# esp-wifisensor.net
KiCad netlist of a schematic drawn in EAGLE
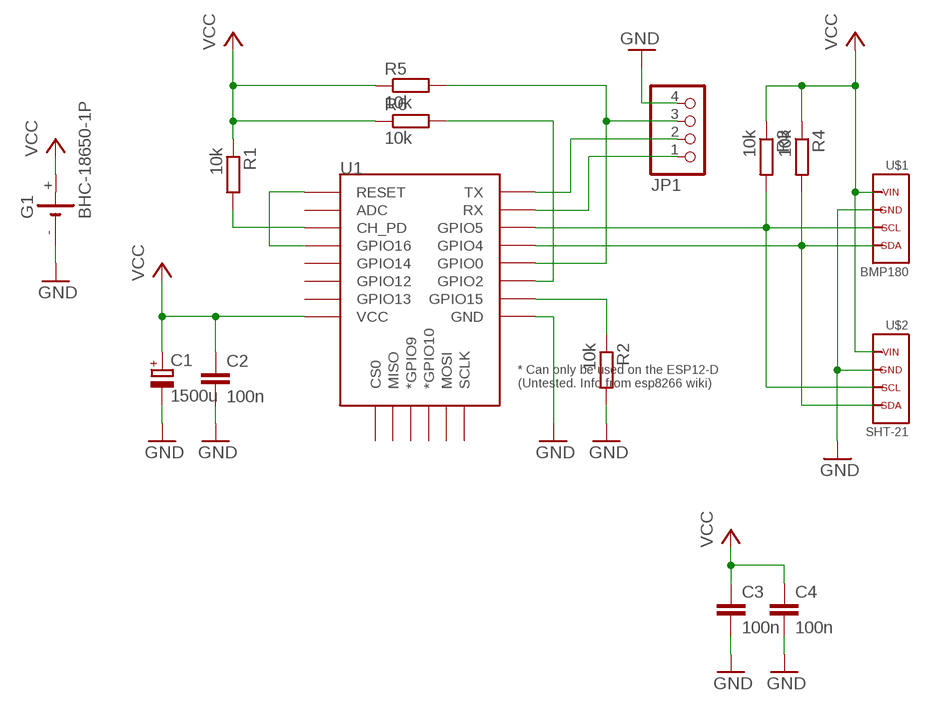
[diagram p0: schematic, sheet 1]

(export (version "E")
  (design (tool "Eeschema 10.0.6"))
  (components
    (comp (ref "C1")
      (value "1500u")
      (footprint "eagle-import:E5-13")
      (libsource (lib "eagle-import") (part "CPOL-EUE5-13"))
    )
    (comp (ref "C2")
      (value "100n")
      (footprint "eagle-import:C1206K")
      (libsource (lib "eagle-import") (part "C-EUC1206K"))
    )
    (comp (ref "C3")
      (value "100n")
      (footprint "eagle-import:C1206K")
      (libsource (lib "eagle-import") (part "C-EUC1206K"))
    )
    (comp (ref "C4")
      (value "100n")
      (footprint "eagle-import:C1206K")
      (libsource (lib "eagle-import") (part "C-EUC1206K"))
    )
    (comp (ref "G1")
      (value "BHC-18650-1P")
      (footprint "eagle-import:BHC-18650-1P")
      (libsource (lib "eagle-import") (part "BHC-18650-1P"))
    )
    (comp (ref "JP1")
      (value "PINHD-1X4")
      (footprint "eagle-import:1X04")
      (libsource (lib "eagle-import") (part "PINHD-1X4"))
    )
    (comp (ref "R1")
      (value "10k")
      (footprint "eagle-import:M1206")
      (libsource (lib "eagle-import") (part "R-EU_M1206"))
    )
    (comp (ref "R2")
      (value "10k")
      (footprint "eagle-import:M1206")
      (libsource (lib "eagle-import") (part "R-EU_M1206"))
    )
    (comp (ref "R3")
      (value "10k")
      (footprint "eagle-import:M1206")
      (libsource (lib "eagle-import") (part "R-EU_M1206"))
    )
    (comp (ref "R4")
      (value "10k")
      (footprint "eagle-import:M1206")
      (libsource (lib "eagle-import") (part "R-EU_M1206"))
    )
    (comp (ref "R5")
      (value "10k")
      (footprint "eagle-import:M1206")
      (libsource (lib "eagle-import") (part "R-EU_M1206"))
    )
    (comp (ref "R6")
      (value "10k")
      (footprint "eagle-import:M1206")
      (libsource (lib "eagle-import") (part "R-EU_M1206"))
    )
    (comp (ref "U$1")
      (value "BMP180")
      (footprint "eagle-import:BMP180")
      (libsource (lib "eagle-import") (part "BMP180"))
    )
    (comp (ref "U$2")
      (value "SHT-21")
      (footprint "eagle-import:SHT-21")
      (libsource (lib "eagle-import") (part "SHT-21"))
    )
    (comp (ref "U1")
      (value "ESP12ESMD")
      (footprint "eagle-import:ESP12E-SMD")
      (libsource (lib "eagle-import") (part "ESP12ESMD"))
    )
  )
  (nets
    (net (code "1") (name "GND") (class "Default")
      (node (ref "C1") (pin "-") (pinfunction "-_-") (pintype "passive"))
      (node (ref "C2") (pin "2") (pinfunction "2_2") (pintype "passive"))
      (node (ref "C3") (pin "2") (pinfunction "2_2") (pintype "passive"))
      (node (ref "C4") (pin "2") (pinfunction "2_2") (pintype "passive"))
      (node (ref "G1") (pin "-") (pinfunction "-_-") (pintype "passive"))
      (node (ref "JP1") (pin "4") (pinfunction "4_4") (pintype "passive"))
      (node (ref "R2") (pin "2") (pinfunction "2_2") (pintype "passive"))
      (node (ref "U$1") (pin "GND") (pinfunction "GND_GND") (pintype "bidirectional"))
      (node (ref "U$2") (pin "GND") (pinfunction "GND_GND") (pintype "bidirectional"))
      (node (ref "U1") (pin "GND") (pinfunction "GND_GND") (pintype "bidirectional"))
    )
    (net (code "2") (name "Net-(JP1-Pad3)") (class "Default")
      (node (ref "JP1") (pin "3") (pinfunction "3_3") (pintype "passive"))
      (node (ref "R5") (pin "2") (pinfunction "2_2") (pintype "passive"))
      (node (ref "U1") (pin "GPIO0") (pinfunction "GPIO0_GPIO0") (pintype "bidirectional"))
    )
    (net (code "3") (name "Net-(R1-Pad2)") (class "Default")
      (node (ref "R1") (pin "2") (pinfunction "2_2") (pintype "passive"))
      (node (ref "U1") (pin "CH_PD") (pinfunction "CH_PD_CH_PD") (pintype "bidirectional"))
    )
    (net (code "4") (name "Net-(R2-Pad1)") (class "Default")
      (node (ref "R2") (pin "1") (pinfunction "1_1") (pintype "passive"))
      (node (ref "U1") (pin "GPIO15") (pinfunction "GPIO15_GPIO15") (pintype "bidirectional"))
    )
    (net (code "5") (name "Net-(R3-Pad2)") (class "Default")
      (node (ref "R3") (pin "2") (pinfunction "2_2") (pintype "passive"))
      (node (ref "U$1") (pin "SCL") (pinfunction "SCL_SCL") (pintype "bidirectional"))
      (node (ref "U$2") (pin "SCL") (pinfunction "SCL_SCL") (pintype "bidirectional"))
      (node (ref "U1") (pin "GPIO5") (pinfunction "GPIO5_GPIO5") (pintype "bidirectional"))
    )
    (net (code "6") (name "Net-(R4-Pad2)") (class "Default")
      (node (ref "R4") (pin "2") (pinfunction "2_2") (pintype "passive"))
      (node (ref "U$1") (pin "SDA") (pinfunction "SDA_SDA") (pintype "bidirectional"))
      (node (ref "U$2") (pin "SDA") (pinfunction "SDA_SDA") (pintype "bidirectional"))
      (node (ref "U1") (pin "GPIO4") (pinfunction "GPIO4_GPIO4") (pintype "bidirectional"))
    )
    (net (code "7") (name "Net-(R6-Pad2)") (class "Default")
      (node (ref "R6") (pin "2") (pinfunction "2_2") (pintype "passive"))
      (node (ref "U1") (pin "GPIO2") (pinfunction "GPIO2_GPIO2") (pintype "bidirectional"))
    )
    (net (code "8") (name "Net-(U1-PadGPIO16)") (class "Default")
      (node (ref "U1") (pin "GPIO16") (pinfunction "GPIO16_GPIO16") (pintype "bidirectional"))
      (node (ref "U1") (pin "RESET") (pinfunction "RESET_RESET") (pintype "bidirectional"))
    )
    (net (code "9") (name "Net-(U1-RX)") (class "Default")
      (node (ref "JP1") (pin "1") (pinfunction "1_1") (pintype "passive"))
      (node (ref "U1") (pin "RXD0") (pinfunction "RX_RXD0") (pintype "bidirectional"))
    )
    (net (code "10") (name "Net-(U1-TX)") (class "Default")
      (node (ref "JP1") (pin "2") (pinfunction "2_2") (pintype "passive"))
      (node (ref "U1") (pin "TXD0") (pinfunction "TX_TXD0") (pintype "bidirectional"))
    )
    (net (code "11") (name "VCC") (class "Default")
      (node (ref "C1") (pin "+") (pinfunction "+_+") (pintype "passive"))
      (node (ref "C2") (pin "1") (pinfunction "1_1") (pintype "passive"))
      (node (ref "C3") (pin "1") (pinfunction "1_1") (pintype "passive"))
      (node (ref "C4") (pin "1") (pinfunction "1_1") (pintype "passive"))
      (node (ref "G1") (pin "+") (pinfunction "+_+") (pintype "passive"))
      (node (ref "R1") (pin "1") (pinfunction "1_1") (pintype "passive"))
      (node (ref "R3") (pin "1") (pinfunction "1_1") (pintype "passive"))
      (node (ref "R4") (pin "1") (pinfunction "1_1") (pintype "passive"))
      (node (ref "R5") (pin "1") (pinfunction "1_1") (pintype "passive"))
      (node (ref "R6") (pin "1") (pinfunction "1_1") (pintype "passive"))
      (node (ref "U$1") (pin "VIN") (pinfunction "VIN_VIN") (pintype "bidirectional"))
      (node (ref "U$2") (pin "VIN") (pinfunction "VIN_VIN") (pintype "bidirectional"))
      (node (ref "U1") (pin "VCC") (pinfunction "VCC_VCC") (pintype "bidirectional"))
    )
    (net (code "12") (name "unconnected-(U1-*GPIO9-PadGPIO9)") (class "Default")
      (node (ref "U1") (pin "GPIO9") (pinfunction "*GPIO9_GPIO9") (pintype "bidirectional"))
    )
    (net (code "13") (name "unconnected-(U1-*GPIO10-PadGPIO10)") (class "Default")
      (node (ref "U1") (pin "GPIO10") (pinfunction "*GPIO10_GPIO10") (pintype "bidirectional"))
    )
    (net (code "14") (name "unconnected-(U1-PadADC)") (class "Default")
      (node (ref "U1") (pin "ADC") (pinfunction "ADC_ADC") (pintype "bidirectional"))
    )
    (net (code "15") (name "unconnected-(U1-PadCS0)") (class "Default")
      (node (ref "U1") (pin "CS0") (pinfunction "CS0_CS0") (pintype "bidirectional"))
    )
    (net (code "16") (name "unconnected-(U1-PadGPIO12)") (class "Default")
      (node (ref "U1") (pin "GPIO12") (pinfunction "GPIO12_GPIO12") (pintype "bidirectional"))
    )
    (net (code "17") (name "unconnected-(U1-PadGPIO13)") (class "Default")
      (node (ref "U1") (pin "GPIO13") (pinfunction "GPIO13_GPIO13") (pintype "bidirectional"))
    )
    (net (code "18") (name "unconnected-(U1-PadGPIO14)") (class "Default")
      (node (ref "U1") (pin "GPIO14") (pinfunction "GPIO14_GPIO14") (pintype "bidirectional"))
    )
    (net (code "19") (name "unconnected-(U1-PadMISO)") (class "Default")
      (node (ref "U1") (pin "MISO") (pinfunction "MISO_MISO") (pintype "bidirectional"))
    )
    (net (code "20") (name "unconnected-(U1-PadMOSI)") (class "Default")
      (node (ref "U1") (pin "MOSI") (pinfunction "MOSI_MOSI") (pintype "bidirectional"))
    )
    (net (code "21") (name "unconnected-(U1-PadSCLK)") (class "Default")
      (node (ref "U1") (pin "SCLK") (pinfunction "SCLK_SCLK") (pintype "bidirectional"))
    )
  )
)
